# LIDO-HW_200_MCU_SWD_Reset.net
KiCad netlist of a schematic drawn in Altium Designer
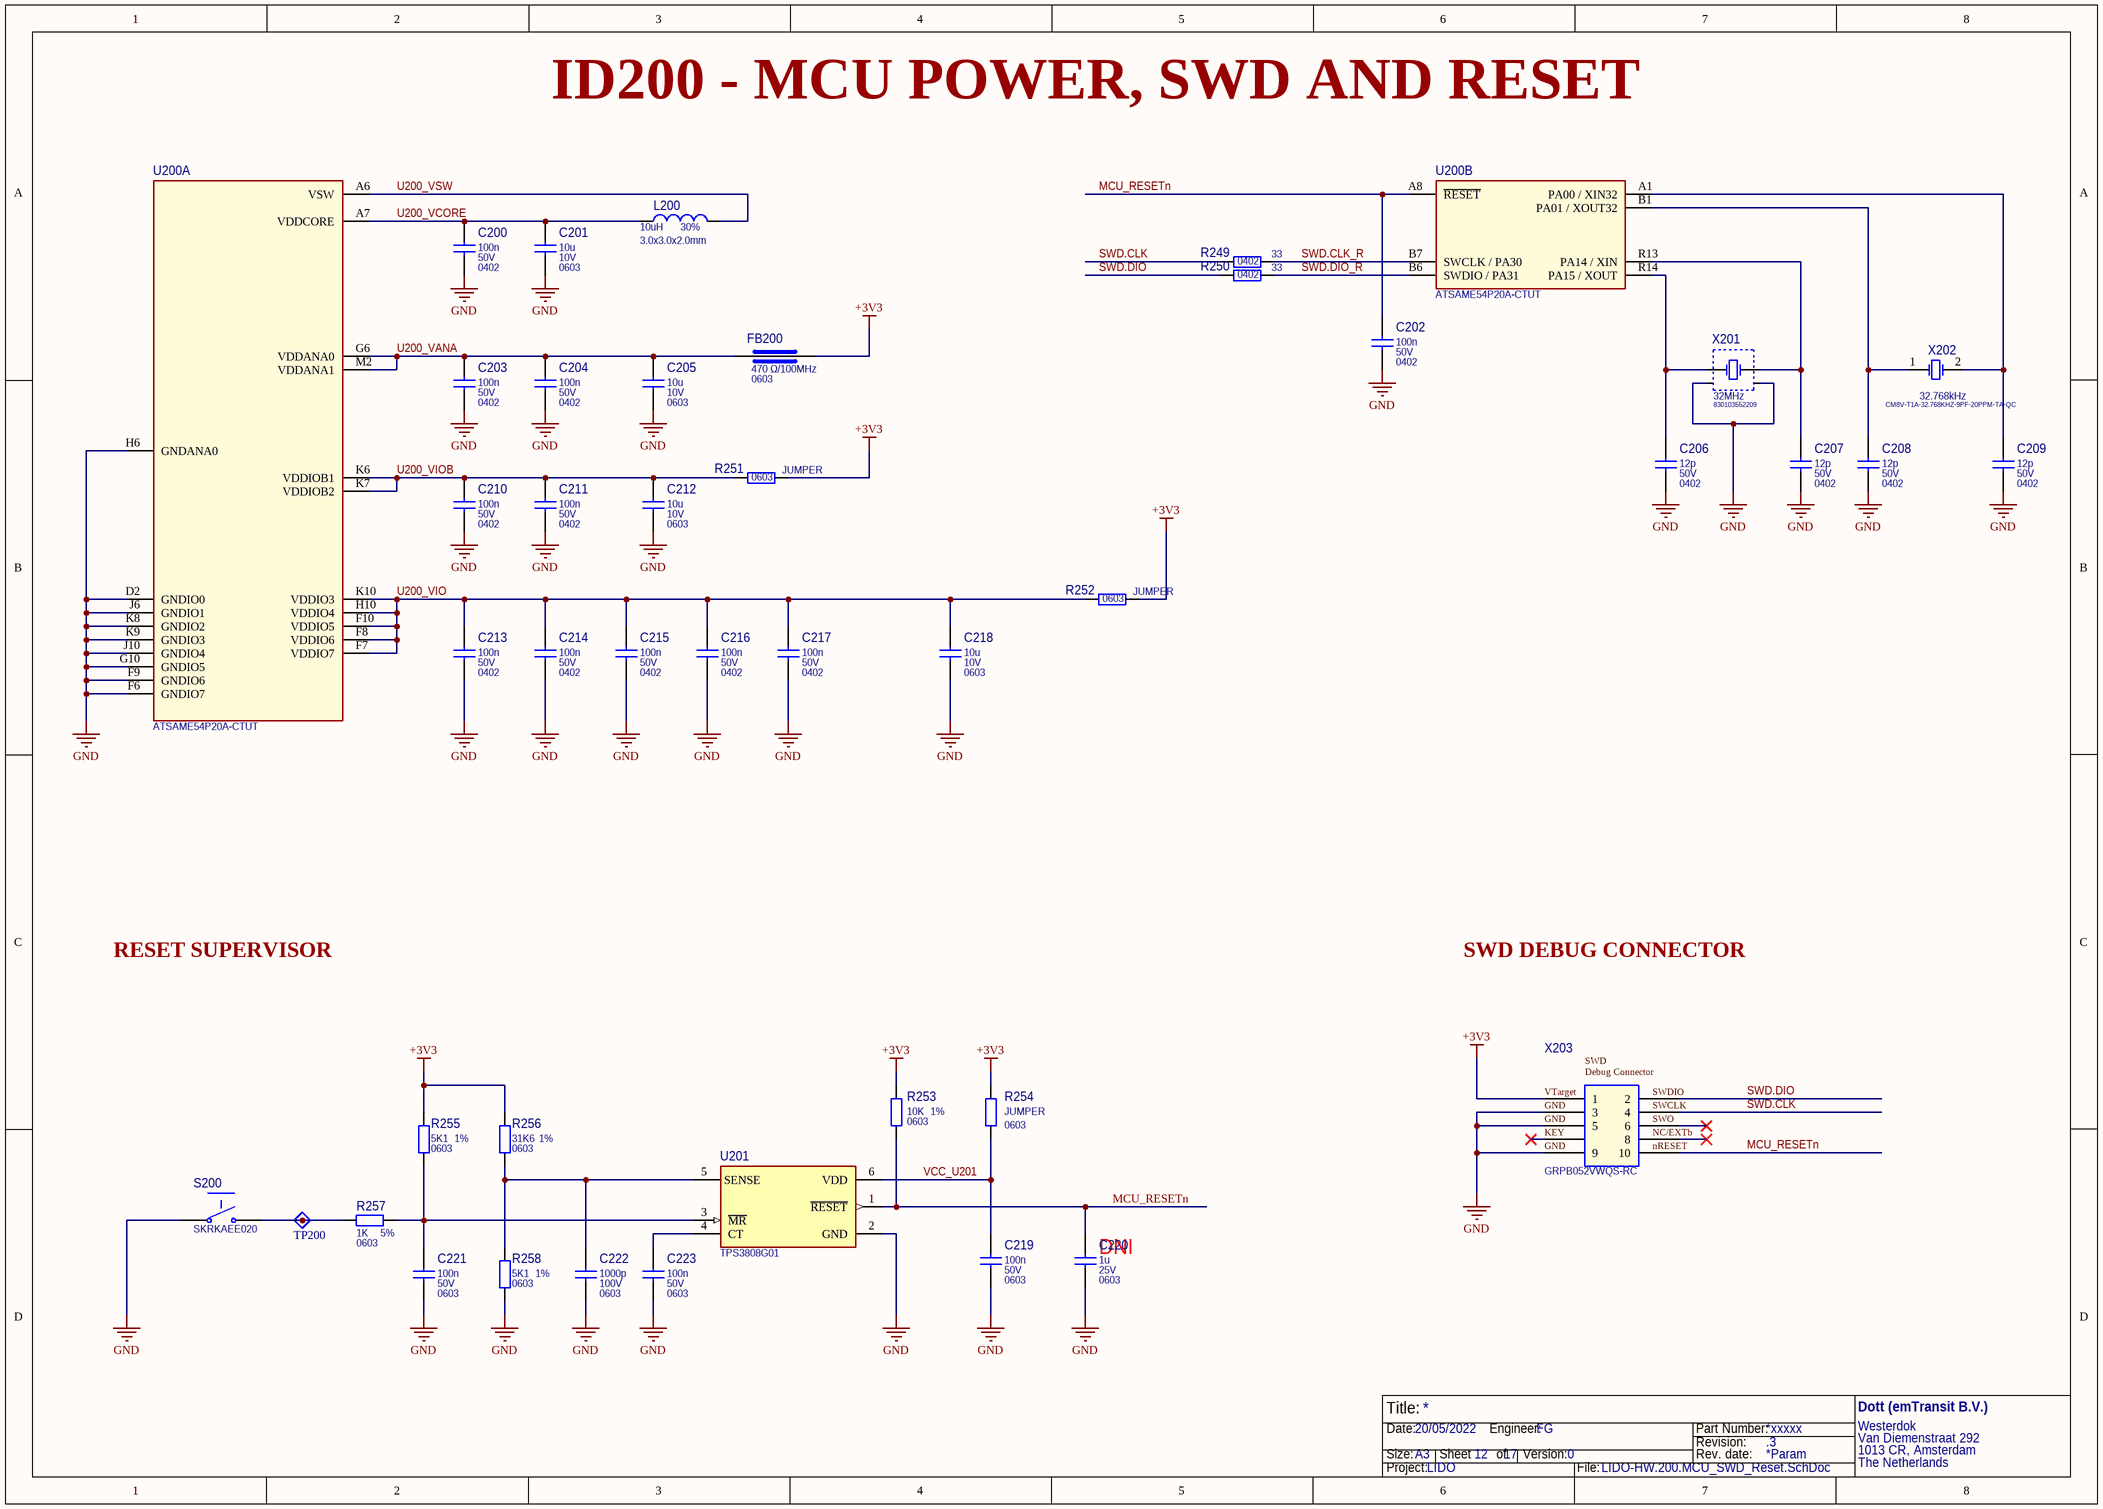
[diagram p0: LIDO-HW.200.MCU_SWD_Reset.SchDoc]

(export (version "E")
  (design (tool "Eeschema 10.0.6"))
  (components
    (comp (ref "C200")
      (value "100n")
      (footprint "CAP_0402_1005X60-N_MURATA_A")
      (description "CAP CER 0.1UF 50V X7R 0402")
      (fields
        (field (name "MANUFACTURER PART NUMBER") "GCM155R71H104KE02D")
        (field (name "MANUFACTURER") "Murata Electronics")
        (field (name "PART VALUE 2") "50V")
        (field (name "PART PACKAGE") "0402")
      )
      (libsource (lib "DB_Library") (part "Ceramic"))
    )
    (comp (ref "C201")
      (value "10u")
      (footprint "CAP_0603_1608X90-N_MURATA_A")
      (description "CAP CER 10UF 10V X7R 0603")
      (fields
        (field (name "MANUFACTURER PART NUMBER") "GRM188Z71A106KA73D")
        (field (name "MANUFACTURER") "Murata Electronics")
        (field (name "PART VALUE 2") "10V")
        (field (name "PART PACKAGE") "0603")
      )
      (libsource (lib "DB_Library") (part "Ceramic"))
    )
    (comp (ref "C202")
      (value "100n")
      (footprint "CAP_0402_1005X60-N_MURATA_A")
      (description "CAP CER 0.1UF 50V X7R 0402")
      (fields
        (field (name "MANUFACTURER PART NUMBER") "GCM155R71H104KE02D")
        (field (name "MANUFACTURER") "Murata Electronics")
        (field (name "PART VALUE 2") "50V")
        (field (name "PART PACKAGE") "0402")
      )
      (libsource (lib "DB_Library") (part "Ceramic"))
    )
    (comp (ref "C203")
      (value "100n")
      (footprint "CAP_0402_1005X60-N_MURATA_A")
      (description "CAP CER 0.1UF 50V X7R 0402")
      (fields
        (field (name "MANUFACTURER PART NUMBER") "GCM155R71H104KE02D")
        (field (name "MANUFACTURER") "Murata Electronics")
        (field (name "PART VALUE 2") "50V")
        (field (name "PART PACKAGE") "0402")
      )
      (libsource (lib "DB_Library") (part "Ceramic"))
    )
    (comp (ref "C204")
      (value "100n")
      (footprint "CAP_0402_1005X60-N_MURATA_A")
      (description "CAP CER 0.1UF 50V X7R 0402")
      (fields
        (field (name "MANUFACTURER PART NUMBER") "GCM155R71H104KE02D")
        (field (name "MANUFACTURER") "Murata Electronics")
        (field (name "PART VALUE 2") "50V")
        (field (name "PART PACKAGE") "0402")
      )
      (libsource (lib "DB_Library") (part "Ceramic"))
    )
    (comp (ref "C205")
      (value "10u")
      (footprint "CAP_0603_1608X90-N_MURATA_A")
      (description "CAP CER 10UF 10V X7R 0603")
      (fields
        (field (name "MANUFACTURER PART NUMBER") "GRM188Z71A106KA73D")
        (field (name "MANUFACTURER") "Murata Electronics")
        (field (name "PART VALUE 2") "10V")
        (field (name "PART PACKAGE") "0603")
      )
      (libsource (lib "DB_Library") (part "Ceramic"))
    )
    (comp (ref "C206")
      (value "12p")
      (footprint "CAP_0402_1005X60-N_MURATA_A")
      (description "CAP CER 12PF 50V C0G/NP0 0402")
      (fields
        (field (name "MANUFACTURER PART NUMBER") "GJM1555C1H120FB01D")
        (field (name "MANUFACTURER") "Murata Electronics")
        (field (name "PART VALUE 2") "50V")
        (field (name "PART PACKAGE") "0402")
      )
      (libsource (lib "DB_Library") (part "Ceramic"))
    )
    (comp (ref "C207")
      (value "12p")
      (footprint "CAP_0402_1005X60-N_MURATA_A")
      (description "CAP CER 12PF 50V C0G/NP0 0402")
      (fields
        (field (name "MANUFACTURER PART NUMBER") "GJM1555C1H120FB01D")
        (field (name "MANUFACTURER") "Murata Electronics")
        (field (name "PART VALUE 2") "50V")
        (field (name "PART PACKAGE") "0402")
      )
      (libsource (lib "DB_Library") (part "Ceramic"))
    )
    (comp (ref "C208")
      (value "12p")
      (footprint "CAP_0402_1005X60-N_MURATA_A")
      (description "CAP CER 12PF 50V C0G/NP0 0402")
      (fields
        (field (name "MANUFACTURER PART NUMBER") "GJM1555C1H120FB01D")
        (field (name "MANUFACTURER") "Murata Electronics")
        (field (name "PART VALUE 2") "50V")
        (field (name "PART PACKAGE") "0402")
      )
      (libsource (lib "DB_Library") (part "Ceramic"))
    )
    (comp (ref "C209")
      (value "12p")
      (footprint "CAP_0402_1005X60-N_MURATA_A")
      (description "CAP CER 12PF 50V C0G/NP0 0402")
      (fields
        (field (name "MANUFACTURER PART NUMBER") "GJM1555C1H120FB01D")
        (field (name "MANUFACTURER") "Murata Electronics")
        (field (name "PART VALUE 2") "50V")
        (field (name "PART PACKAGE") "0402")
      )
      (libsource (lib "DB_Library") (part "Ceramic"))
    )
    (comp (ref "C210")
      (value "100n")
      (footprint "CAP_0402_1005X60-N_MURATA_A")
      (description "CAP CER 0.1UF 50V X7R 0402")
      (fields
        (field (name "MANUFACTURER PART NUMBER") "GCM155R71H104KE02D")
        (field (name "MANUFACTURER") "Murata Electronics")
        (field (name "PART VALUE 2") "50V")
        (field (name "PART PACKAGE") "0402")
      )
      (libsource (lib "DB_Library") (part "Ceramic"))
    )
    (comp (ref "C211")
      (value "100n")
      (footprint "CAP_0402_1005X60-N_MURATA_A")
      (description "CAP CER 0.1UF 50V X7R 0402")
      (fields
        (field (name "MANUFACTURER PART NUMBER") "GCM155R71H104KE02D")
        (field (name "MANUFACTURER") "Murata Electronics")
        (field (name "PART VALUE 2") "50V")
        (field (name "PART PACKAGE") "0402")
      )
      (libsource (lib "DB_Library") (part "Ceramic"))
    )
    (comp (ref "C212")
      (value "10u")
      (footprint "CAP_0603_1608X90-N_MURATA_A")
      (description "CAP CER 10UF 10V X7R 0603")
      (fields
        (field (name "MANUFACTURER PART NUMBER") "GRM188Z71A106KA73D")
        (field (name "MANUFACTURER") "Murata Electronics")
        (field (name "PART VALUE 2") "10V")
        (field (name "PART PACKAGE") "0603")
      )
      (libsource (lib "DB_Library") (part "Ceramic"))
    )
    (comp (ref "C213")
      (value "100n")
      (footprint "CAP_0402_1005X60-N_MURATA_A")
      (description "CAP CER 0.1UF 50V X7R 0402")
      (fields
        (field (name "MANUFACTURER PART NUMBER") "GCM155R71H104KE02D")
        (field (name "MANUFACTURER") "Murata Electronics")
        (field (name "PART VALUE 2") "50V")
        (field (name "PART PACKAGE") "0402")
      )
      (libsource (lib "DB_Library") (part "Ceramic"))
    )
    (comp (ref "C214")
      (value "100n")
      (footprint "CAP_0402_1005X60-N_MURATA_A")
      (description "CAP CER 0.1UF 50V X7R 0402")
      (fields
        (field (name "MANUFACTURER PART NUMBER") "GCM155R71H104KE02D")
        (field (name "MANUFACTURER") "Murata Electronics")
        (field (name "PART VALUE 2") "50V")
        (field (name "PART PACKAGE") "0402")
      )
      (libsource (lib "DB_Library") (part "Ceramic"))
    )
    (comp (ref "C215")
      (value "100n")
      (footprint "CAP_0402_1005X60-N_MURATA_A")
      (description "CAP CER 0.1UF 50V X7R 0402")
      (fields
        (field (name "MANUFACTURER PART NUMBER") "GCM155R71H104KE02D")
        (field (name "MANUFACTURER") "Murata Electronics")
        (field (name "PART VALUE 2") "50V")
        (field (name "PART PACKAGE") "0402")
      )
      (libsource (lib "DB_Library") (part "Ceramic"))
    )
    (comp (ref "C216")
      (value "100n")
      (footprint "CAP_0402_1005X60-N_MURATA_A")
      (description "CAP CER 0.1UF 50V X7R 0402")
      (fields
        (field (name "MANUFACTURER PART NUMBER") "GCM155R71H104KE02D")
        (field (name "MANUFACTURER") "Murata Electronics")
        (field (name "PART VALUE 2") "50V")
        (field (name "PART PACKAGE") "0402")
      )
      (libsource (lib "DB_Library") (part "Ceramic"))
    )
    (comp (ref "C217")
      (value "100n")
      (footprint "CAP_0402_1005X60-N_MURATA_A")
      (description "CAP CER 0.1UF 50V X7R 0402")
      (fields
        (field (name "MANUFACTURER PART NUMBER") "GCM155R71H104KE02D")
        (field (name "MANUFACTURER") "Murata Electronics")
        (field (name "PART VALUE 2") "50V")
        (field (name "PART PACKAGE") "0402")
      )
      (libsource (lib "DB_Library") (part "Ceramic"))
    )
    (comp (ref "C218")
      (value "10u")
      (footprint "CAP_0603_1608X90-N_MURATA_A")
      (description "CAP CER 10UF 10V X7R 0603")
      (fields
        (field (name "MANUFACTURER PART NUMBER") "GRM188Z71A106KA73D")
        (field (name "MANUFACTURER") "Murata Electronics")
        (field (name "PART VALUE 2") "10V")
        (field (name "PART PACKAGE") "0603")
      )
      (libsource (lib "DB_Library") (part "Ceramic"))
    )
    (comp (ref "C219")
      (value "100n")
      (footprint "CAP_0603_1608X90-N_MURATA_A")
      (description "CAP CER 0.1UF 50V X7R 0603")
      (fields
        (field (name "MANUFACTURER PART NUMBER") "CGA3E2X7R1H104K080AA")
        (field (name "MANUFACTURER") "TDK Corporation")
        (field (name "PART VALUE 2") "50V")
        (field (name "PART PACKAGE") "0603")
      )
      (libsource (lib "DB_Library") (part "Ceramic"))
    )
    (comp (ref "C220")
      (value "1u")
      (footprint "CAP_0603_1608X90-N_MURATA_A")
      (description "CAP CER 1UF 25V X7R 0603")
      (fields
        (field (name "MANUFACTURER PART NUMBER") "CGA3E1X7R1E105M080AE")
        (field (name "MANUFACTURER") "TDK Corporation")
        (field (name "PART VALUE 2") "25V")
        (field (name "PART PACKAGE") "0603")
      )
      (libsource (lib "DB_Library") (part "Ceramic"))
    )
    (comp (ref "C221")
      (value "100n")
      (footprint "CAP_0603_1608X90-N_MURATA_A")
      (description "CAP CER 0.1UF 50V X7R 0603")
      (fields
        (field (name "MANUFACTURER PART NUMBER") "CGA3E2X7R1H104K080AA")
        (field (name "MANUFACTURER") "TDK Corporation")
        (field (name "PART VALUE 2") "50V")
        (field (name "PART PACKAGE") "0603")
      )
      (libsource (lib "DB_Library") (part "Ceramic"))
    )
    (comp (ref "C222")
      (value "1000p")
      (footprint "CAP_0603_1608X90-N_MURATA_A")
      (description "CAP CER 1000PF 100V X7R 0603")
      (fields
        (field (name "MANUFACTURER PART NUMBER") "CGA3E2X7R2A102K080AA")
        (field (name "MANUFACTURER") "TDK Corporation")
        (field (name "PART VALUE 2") "100V")
        (field (name "PART PACKAGE") "0603")
      )
      (libsource (lib "DB_Library") (part "Ceramic"))
    )
    (comp (ref "C223")
      (value "100n")
      (footprint "CAP_0603_1608X90-N_MURATA_A")
      (description "CAP CER 0.1UF 50V X7R 0603")
      (fields
        (field (name "MANUFACTURER PART NUMBER") "CGA3E2X7R1H104K080AA")
        (field (name "MANUFACTURER") "TDK Corporation")
        (field (name "PART VALUE 2") "50V")
        (field (name "PART PACKAGE") "0603")
      )
      (libsource (lib "DB_Library") (part "Ceramic"))
    )
    (comp (ref "FB200")
      (value "470 Ω/100MHz")
      (footprint "IND_0603_1608X95-N_AVX_A")
      (description "FERRITE BEAD 470 OHM 0603 1LN")
      (fields
        (field (name "MANUFACTURER PART NUMBER") "BLM18PG471SN1D")
        (field (name "MANUFACTURER") "Murata Electronics")
        (field (name "PART PACKAGE") "0603")
      )
      (libsource (lib "DB_Library") (part "FERRITE_BEAD"))
    )
    (comp (ref "L200")
      (value "10uH")
      (footprint "SUMIDA_CDRH2D18_HP_A")
      (description "FIXED IND 10UH 900MA 245MOHM SMD")
      (fields
        (field (name "MANUFACTURER PART NUMBER") "CDRH2D18/HPNP-100NC")
        (field (name "MANUFACTURER") "Sumida America Components Inc.")
        (field (name "PART VALUE 2") "30%")
        (field (name "PART PACKAGE") "3.0x3.0x2.0mm")
      )
      (libsource (lib "DB_Library") (part "Inductor"))
    )
    (comp (ref "R249")
      (value "33")
      (footprint "RES_0402_1005X40-N_YAGEO_A")
      (description "RES SMD 33 OHM 5% 1/10W 0402")
      (fields
        (field (name "MANUFACTURER PART NUMBER") "ERJ-2GEJ330X")
        (field (name "MANUFACTURER") "Panasonic Electronic Components")
        (field (name "PART PACKAGE") "0402")
      )
      (libsource (lib "") (part "Resistor_2"))
    )
    (comp (ref "R250")
      (value "33")
      (footprint "RES_0402_1005X40-N_YAGEO_A")
      (description "RES SMD 33 OHM 5% 1/10W 0402")
      (fields
        (field (name "MANUFACTURER PART NUMBER") "ERJ-2GEJ330X")
        (field (name "MANUFACTURER") "Panasonic Electronic Components")
        (field (name "PART PACKAGE") "0402")
      )
      (libsource (lib "") (part "Resistor_2"))
    )
    (comp (ref "R251")
      (value "JUMPER")
      (footprint "RES_0603_1608X60-N_YAGEO_A")
      (description "RES 0 OHM JUMPER 1/10W 0603")
      (fields
        (field (name "MANUFACTURER PART NUMBER") "RC0603JR-070RL")
        (field (name "MANUFACTURER") "YAGEO")
        (field (name "PART PACKAGE") "0603")
      )
      (libsource (lib "") (part "Resistor_2"))
    )
    (comp (ref "R252")
      (value "JUMPER")
      (footprint "RES_0603_1608X60-N_YAGEO_A")
      (description "RES 0 OHM JUMPER 1/10W 0603")
      (fields
        (field (name "MANUFACTURER PART NUMBER") "RC0603JR-070RL")
        (field (name "MANUFACTURER") "YAGEO")
        (field (name "PART PACKAGE") "0603")
      )
      (libsource (lib "") (part "Resistor_2"))
    )
    (comp (ref "R253")
      (value "10K")
      (footprint "RES_0603_1608X60-N_YAGEO_A")
      (description "RES 10K OHM 1% 1/10W 0603")
      (fields
        (field (name "MANUFACTURER PART NUMBER") "RC0603FR-0710KL")
        (field (name "MANUFACTURER") "YAGEO")
        (field (name "PART VALUE 2") "1%")
        (field (name "PART PACKAGE") "0603")
      )
      (libsource (lib "DB_Library") (part "Resistor"))
    )
    (comp (ref "R254")
      (value "JUMPER")
      (footprint "RES_0603_1608X60-N_YAGEO_A")
      (description "RES 0 OHM JUMPER 1/10W 0603")
      (fields
        (field (name "MANUFACTURER PART NUMBER") "RC0603JR-070RL")
        (field (name "MANUFACTURER") "YAGEO")
        (field (name "PART PACKAGE") "0603")
      )
      (libsource (lib "DB_Library") (part "Resistor"))
    )
    (comp (ref "R255")
      (value "5K1")
      (footprint "RES_0603_1608X60-N_YAGEO_A")
      (description "RES SMD 5.1K OHM 1% 1/10W 0603")
      (fields
        (field (name "MANUFACTURER PART NUMBER") "ERJ-3EKF5101V")
        (field (name "MANUFACTURER") "Panasonic Electronic Components")
        (field (name "PART VALUE 2") "1%")
        (field (name "PART PACKAGE") "0603")
      )
      (libsource (lib "DB_Library") (part "Resistor"))
    )
    (comp (ref "R256")
      (value "31K6")
      (footprint "RES_0603_1608X60-N_YAGEO_A")
      (description "RES 31.6K OHM 1% 1/10W 0603")
      (fields
        (field (name "MANUFACTURER PART NUMBER") "RC0603FR-0731K6L")
        (field (name "MANUFACTURER") "YAGEO")
        (field (name "PART VALUE 2") "1%")
        (field (name "PART PACKAGE") "0603")
      )
      (libsource (lib "DB_Library") (part "Resistor"))
    )
    (comp (ref "R257")
      (value "1K")
      (footprint "RES_0603_1608X60-N_YAGEO_A")
      (description "RES 1K OHM 5% 1/10W 0603")
      (fields
        (field (name "MANUFACTURER PART NUMBER") "RC0603JR-071KL")
        (field (name "MANUFACTURER") "YAGEO")
        (field (name "PART VALUE 2") "5%")
        (field (name "PART PACKAGE") "0603")
      )
      (libsource (lib "") (part "Resistor_1"))
    )
    (comp (ref "R258")
      (value "5K1")
      (footprint "RES_0603_1608X60-N_YAGEO_A")
      (description "RES SMD 5.1K OHM 1% 1/10W 0603")
      (fields
        (field (name "MANUFACTURER PART NUMBER") "ERJ-3EKF5101V")
        (field (name "MANUFACTURER") "Panasonic Electronic Components")
        (field (name "PART VALUE 2") "1%")
        (field (name "PART PACKAGE") "0603")
      )
      (libsource (lib "DB_Library") (part "Resistor"))
    )
    (comp (ref "S200")
      (value "SKRKAEE020")
      (footprint "ALPS_SKRKA_390X290X200_A")
      (description "Switch Tactile N.O. SPST Round Button Gull Wing 0.05A 12VDC 1.57N SMD T/R")
      (fields (field (name "MANUFACTURER") "Alps Alpine") (field (name "OBSOLETE PART") "False"))
      (libsource (lib "DB_Library") (part "TactileSwitch_SPST_NO_A"))
    )
    (comp (ref "TP200")
      (value "TestPoint_A")
      (footprint "TESTPOINT_1D_A")
      (description "Pad Diamater 1mm")
      (fields (field (name "PART") "Test Point 1D A") (field (name "OBSOLETE PART") "False"))
      (libsource (lib "DB_Library") (part "TestPoint_A"))
    )
    (comp (ref "U200")
      (value "ATSAME54P20A-CTUT")
      (footprint "BGA120CP50_15X15_800X800X120B25-N_MICROCHIP_A")
      (fields (field (name "MANUFACTURER") "Microchip Technology") (field (name "OBSOLETE PART") "False"))
      (libsource (lib "") (part "ATMEL_ATSAME54P20A-CT_A_1"))
    )
    (comp (ref "U201")
      (value "TPS3808G01")
      (footprint "SOT23-6P95_280X145L45-N_TI_A")
      (description "Supervisor Open Drain or Open Collector 1 Channel SOT-23-6")
      (fields
        (field (name "MANUFACTURER") "Texas Instruments")
        (field (name "MANUFACTURER PART NUMBER") "TPS3808G01DBVR")
        (field (name "DESIGNER") "Matt Drazenovich")
        (field (name "REVIEWED") "Dekimo_30-06-2020")
      )
      (libsource (lib "DB_Library") (part "TPS3808_A"))
    )
    (comp (ref "X201")
      (value "32MHz")
      (footprint "IQD_CFPX180_340X270X80_A")
      (description "32 MHz ±10ppm Crystal 9pF 40 Ohms 4-SMD, No Lead")
      (fields
        (field (name "MANUFACTURER PART NUMBER") "830103552209")
        (field (name "MANUFACTURER") "Würth Elektronik")
        (field (name "OBSOLETE PART") "False")
      )
      (libsource (lib "DB_Library") (part "XTAL_4Pins_A"))
    )
    (comp (ref "X202")
      (value "32.768kHz")
      (footprint "ECS_ECX-12Q_200x120x55_A")
      (description "32.768 kHz ±20ppm Crystal 9pF 70 kOhms 2-SMD, No Lead")
      (fields
        (field (name "MANUFACTURER PART NUMBER") "CM8V-T1A-32.768KHZ-9PF-20PPM-TA-QC")
        (field (name "MANUFACTURER") "Micro Crystal AG")
        (field (name "OBSOLETE PART") "False")
      )
      (libsource (lib "DB_Library") (part "XTAL_2PINS_A"))
    )
    (comp (ref "X203")
      (value "GRPB052VWQS-RC")
      (footprint "SAMTEC_FTSH-105-01-L-DV_A")
      (description "CONN HEADER SMD 10POS 1.27MM")
      (fields
        (field (name "MANUFACTURER") "Sullins Connector Solutions")
        (field (name "OBSOLETE PART") "False")
      )
      (libsource (lib "DB_Library") (part "10Pin SWD Interface"))
    )
  )
  (nets
    (net (code "1") (name "+3V3") (class "Default")
      (node (ref "FB200") (pin "2") (pinfunction "2_2") (pintype "passive"))
      (node (ref "R251") (pin "2") (pinfunction "2_2") (pintype "passive"))
      (node (ref "R252") (pin "2") (pinfunction "2_2") (pintype "passive"))
      (node (ref "R253") (pin "2") (pinfunction "2_2") (pintype "passive"))
      (node (ref "R254") (pin "2") (pinfunction "2_2") (pintype "passive"))
      (node (ref "R255") (pin "2") (pinfunction "2_2") (pintype "passive"))
      (node (ref "R256") (pin "2") (pinfunction "2_2") (pintype "passive"))
      (node (ref "X203") (pin "1") (pinfunction "1_1") (pintype "passive"))
    )
    (net (code "2") (name "/MCU_RESETn") (class "Default")
      (node (ref "C202") (pin "1") (pinfunction "1_1") (pintype "passive"))
      (node (ref "C220") (pin "1") (pinfunction "1_1") (pintype "passive"))
      (node (ref "R253") (pin "1") (pinfunction "1_1") (pintype "passive"))
      (node (ref "U200") (pin "A8") (pinfunction "~{RESET}_A8") (pintype "passive"))
      (node (ref "U201") (pin "1") (pinfunction "~{RESET}_1") (pintype "output"))
      (node (ref "X203") (pin "10") (pinfunction "10_10") (pintype "passive"))
    )
    (net (code "3") (name "/SWD.CLK") (class "Default")
      (node (ref "R249") (pin "1") (pinfunction "1_1") (pintype "passive"))
      (node (ref "X203") (pin "4") (pinfunction "4_4") (pintype "passive"))
    )
    (net (code "4") (name "/SWD.CLK_R") (class "Default")
      (node (ref "R249") (pin "2") (pinfunction "2_2") (pintype "passive"))
      (node (ref "U200") (pin "B7") (pinfunction "SWCLK_/_PA30_B7") (pintype "power_in"))
    )
    (net (code "5") (name "/SWD.DIO") (class "Default")
      (node (ref "R250") (pin "1") (pinfunction "1_1") (pintype "passive"))
      (node (ref "X203") (pin "2") (pinfunction "2_2") (pintype "passive"))
    )
    (net (code "6") (name "/SWD.DIO_R") (class "Default")
      (node (ref "R250") (pin "2") (pinfunction "2_2") (pintype "passive"))
      (node (ref "U200") (pin "B6") (pinfunction "SWDIO_/_PA31_B6") (pintype "power_in"))
    )
    (net (code "7") (name "/U200_VANA") (class "Default")
      (node (ref "C203") (pin "1") (pinfunction "1_1") (pintype "passive"))
      (node (ref "C204") (pin "1") (pinfunction "1_1") (pintype "passive"))
      (node (ref "C205") (pin "1") (pinfunction "1_1") (pintype "passive"))
      (node (ref "FB200") (pin "1") (pinfunction "1_1") (pintype "passive"))
      (node (ref "U200") (pin "G6") (pinfunction "VDDANA0_G6") (pintype "power_in"))
      (node (ref "U200") (pin "M2") (pinfunction "VDDANA1_M2") (pintype "power_in"))
    )
    (net (code "8") (name "/U200_VCORE") (class "Default")
      (node (ref "C200") (pin "1") (pinfunction "1_1") (pintype "passive"))
      (node (ref "C201") (pin "1") (pinfunction "1_1") (pintype "passive"))
      (node (ref "L200") (pin "1") (pinfunction "1_1") (pintype "passive"))
      (node (ref "U200") (pin "A7") (pinfunction "VDDCORE_A7") (pintype "power_in"))
    )
    (net (code "9") (name "/U200_VIO") (class "Default")
      (node (ref "C213") (pin "1") (pinfunction "1_1") (pintype "passive"))
      (node (ref "C214") (pin "1") (pinfunction "1_1") (pintype "passive"))
      (node (ref "C215") (pin "1") (pinfunction "1_1") (pintype "passive"))
      (node (ref "C216") (pin "1") (pinfunction "1_1") (pintype "passive"))
      (node (ref "C217") (pin "1") (pinfunction "1_1") (pintype "passive"))
      (node (ref "C218") (pin "1") (pinfunction "1_1") (pintype "passive"))
      (node (ref "R252") (pin "1") (pinfunction "1_1") (pintype "passive"))
      (node (ref "U200") (pin "F10") (pinfunction "VDDIO5_F10") (pintype "power_in"))
      (node (ref "U200") (pin "F7") (pinfunction "VDDIO7_F7") (pintype "power_in"))
      (node (ref "U200") (pin "F8") (pinfunction "VDDIO6_F8") (pintype "power_in"))
      (node (ref "U200") (pin "H10") (pinfunction "VDDIO4_H10") (pintype "power_in"))
      (node (ref "U200") (pin "K10") (pinfunction "VDDIO3_K10") (pintype "power_in"))
    )
    (net (code "10") (name "/U200_VIOB") (class "Default")
      (node (ref "C210") (pin "1") (pinfunction "1_1") (pintype "passive"))
      (node (ref "C211") (pin "1") (pinfunction "1_1") (pintype "passive"))
      (node (ref "C212") (pin "1") (pinfunction "1_1") (pintype "passive"))
      (node (ref "R251") (pin "1") (pinfunction "1_1") (pintype "passive"))
      (node (ref "U200") (pin "K6") (pinfunction "VDDIOB1_K6") (pintype "power_in"))
      (node (ref "U200") (pin "K7") (pinfunction "VDDIOB2_K7") (pintype "power_in"))
    )
    (net (code "11") (name "/U200_VSW") (class "Default")
      (node (ref "L200") (pin "2") (pinfunction "2_2") (pintype "passive"))
      (node (ref "U200") (pin "A6") (pinfunction "VSW_A6") (pintype "power_in"))
    )
    (net (code "12") (name "/VCC_U201") (class "Default")
      (node (ref "C219") (pin "2") (pinfunction "2_2") (pintype "passive"))
      (node (ref "R254") (pin "1") (pinfunction "1_1") (pintype "passive"))
      (node (ref "U201") (pin "6") (pinfunction "VDD_6") (pintype "power_in"))
    )
    (net (code "13") (name "GND") (class "Default")
      (node (ref "C200") (pin "2") (pinfunction "2_2") (pintype "passive"))
      (node (ref "C201") (pin "2") (pinfunction "2_2") (pintype "passive"))
      (node (ref "C202") (pin "2") (pinfunction "2_2") (pintype "passive"))
      (node (ref "C203") (pin "2") (pinfunction "2_2") (pintype "passive"))
      (node (ref "C204") (pin "2") (pinfunction "2_2") (pintype "passive"))
      (node (ref "C205") (pin "2") (pinfunction "2_2") (pintype "passive"))
      (node (ref "C206") (pin "2") (pinfunction "2_2") (pintype "passive"))
      (node (ref "C207") (pin "2") (pinfunction "2_2") (pintype "passive"))
      (node (ref "C208") (pin "2") (pinfunction "2_2") (pintype "passive"))
      (node (ref "C209") (pin "2") (pinfunction "2_2") (pintype "passive"))
      (node (ref "C210") (pin "2") (pinfunction "2_2") (pintype "passive"))
      (node (ref "C211") (pin "2") (pinfunction "2_2") (pintype "passive"))
      (node (ref "C212") (pin "2") (pinfunction "2_2") (pintype "passive"))
      (node (ref "C213") (pin "2") (pinfunction "2_2") (pintype "passive"))
      (node (ref "C214") (pin "2") (pinfunction "2_2") (pintype "passive"))
      (node (ref "C215") (pin "2") (pinfunction "2_2") (pintype "passive"))
      (node (ref "C216") (pin "2") (pinfunction "2_2") (pintype "passive"))
      (node (ref "C217") (pin "2") (pinfunction "2_2") (pintype "passive"))
      (node (ref "C218") (pin "2") (pinfunction "2_2") (pintype "passive"))
      (node (ref "C219") (pin "1") (pinfunction "1_1") (pintype "passive"))
      (node (ref "C220") (pin "2") (pinfunction "2_2") (pintype "passive"))
      (node (ref "C221") (pin "1") (pinfunction "1_1") (pintype "passive"))
      (node (ref "C222") (pin "2") (pinfunction "2_2") (pintype "passive"))
      (node (ref "C223") (pin "1") (pinfunction "1_1") (pintype "passive"))
      (node (ref "R258") (pin "1") (pinfunction "1_1") (pintype "passive"))
      (node (ref "S200") (pin "1") (pinfunction "1_1") (pintype "passive"))
      (node (ref "U200") (pin "D2") (pinfunction "GNDIO0_D2") (pintype "passive"))
      (node (ref "U200") (pin "F6") (pinfunction "GNDIO7_F6") (pintype "passive"))
      (node (ref "U200") (pin "F9") (pinfunction "GNDIO6_F9") (pintype "passive"))
      (node (ref "U200") (pin "G10") (pinfunction "GNDIO5_G10") (pintype "passive"))
      (node (ref "U200") (pin "H6") (pinfunction "GNDANA0_H6") (pintype "passive"))
      (node (ref "U200") (pin "J10") (pinfunction "GNDIO4_J10") (pintype "passive"))
      (node (ref "U200") (pin "J6") (pinfunction "GNDIO1_J6") (pintype "passive"))
      (node (ref "U200") (pin "K8") (pinfunction "GNDIO2_K8") (pintype "passive"))
      (node (ref "U200") (pin "K9") (pinfunction "GNDIO3_K9") (pintype "passive"))
      (node (ref "U201") (pin "2") (pinfunction "GND_2") (pintype "power_in"))
      (node (ref "X201") (pin "2") (pinfunction "GND_2") (pintype "passive"))
      (node (ref "X201") (pin "4") (pinfunction "GND_4") (pintype "passive"))
      (node (ref "X203") (pin "3") (pinfunction "3_3") (pintype "passive"))
      (node (ref "X203") (pin "5") (pinfunction "5_5") (pintype "passive"))
      (node (ref "X203") (pin "9") (pinfunction "9_9") (pintype "passive"))
    )
    (net (code "14") (name "Net-(TP200-TP)") (class "Default")
      (node (ref "R257") (pin "2") (pinfunction "2_2") (pintype "passive"))
      (node (ref "S200") (pin "2") (pinfunction "2_2") (pintype "passive"))
      (node (ref "TP200") (pin "1") (pinfunction "TP_1") (pintype "passive"))
    )
    (net (code "15") (name "Net-(U200B-PA00_{slash}_XIN32)") (class "Default")
      (node (ref "C209") (pin "1") (pinfunction "1_1") (pintype "passive"))
      (node (ref "U200") (pin "A1") (pinfunction "PA00_/_XIN32_A1") (pintype "power_in"))
      (node (ref "X202") (pin "2") (pinfunction "OSC2_2") (pintype "passive"))
    )
    (net (code "16") (name "Net-(U200B-PA01_{slash}_XOUT32)") (class "Default")
      (node (ref "C208") (pin "1") (pinfunction "1_1") (pintype "passive"))
      (node (ref "U200") (pin "B1") (pinfunction "PA01_/_XOUT32_B1") (pintype "power_in"))
      (node (ref "X202") (pin "1") (pinfunction "OSC1_1") (pintype "passive"))
    )
    (net (code "17") (name "Net-(U200B-PA14_{slash}_XIN)") (class "Default")
      (node (ref "C207") (pin "1") (pinfunction "1_1") (pintype "passive"))
      (node (ref "U200") (pin "R13") (pinfunction "PA14_/_XIN_R13") (pintype "power_in"))
      (node (ref "X201") (pin "3") (pinfunction "OSC2_3") (pintype "passive"))
    )
    (net (code "18") (name "Net-(U200B-PA15_{slash}_XOUT)") (class "Default")
      (node (ref "C206") (pin "1") (pinfunction "1_1") (pintype "passive"))
      (node (ref "U200") (pin "R14") (pinfunction "PA15_/_XOUT_R14") (pintype "power_in"))
      (node (ref "X201") (pin "1") (pinfunction "OSC1_1") (pintype "passive"))
    )
    (net (code "19") (name "Net-(U201-CT)") (class "Default")
      (node (ref "C223") (pin "2") (pinfunction "2_2") (pintype "passive"))
      (node (ref "U201") (pin "4") (pinfunction "CT_4") (pintype "passive"))
    )
    (net (code "20") (name "Net-(U201-SENSE)") (class "Default")
      (node (ref "C222") (pin "1") (pinfunction "1_1") (pintype "passive"))
      (node (ref "R256") (pin "1") (pinfunction "1_1") (pintype "passive"))
      (node (ref "R258") (pin "2") (pinfunction "2_2") (pintype "passive"))
      (node (ref "U201") (pin "5") (pinfunction "SENSE_5") (pintype "passive"))
    )
    (net (code "21") (name "Net-(U201-~{MR})") (class "Default")
      (node (ref "C221") (pin "2") (pinfunction "2_2") (pintype "passive"))
      (node (ref "R255") (pin "1") (pinfunction "1_1") (pintype "passive"))
      (node (ref "R257") (pin "1") (pinfunction "1_1") (pintype "passive"))
      (node (ref "U201") (pin "3") (pinfunction "~{MR}_3") (pintype "input"))
    )
    (net (code "22") (name "unconnected-(X203-Pad6)") (class "Default")
      (node (ref "X203") (pin "6") (pinfunction "6_6") (pintype "passive+no_connect"))
    )
    (net (code "23") (name "unconnected-(X203-Pad7)") (class "Default")
      (node (ref "X203") (pin "7") (pinfunction "7_7") (pintype "passive+no_connect"))
    )
    (net (code "24") (name "unconnected-(X203-Pad8)") (class "Default")
      (node (ref "X203") (pin "8") (pinfunction "8_8") (pintype "passive+no_connect"))
    )
  )
)
